# SCH_Front_Buzzer.net
KiCad netlist of a schematic drawn in Altium Designer
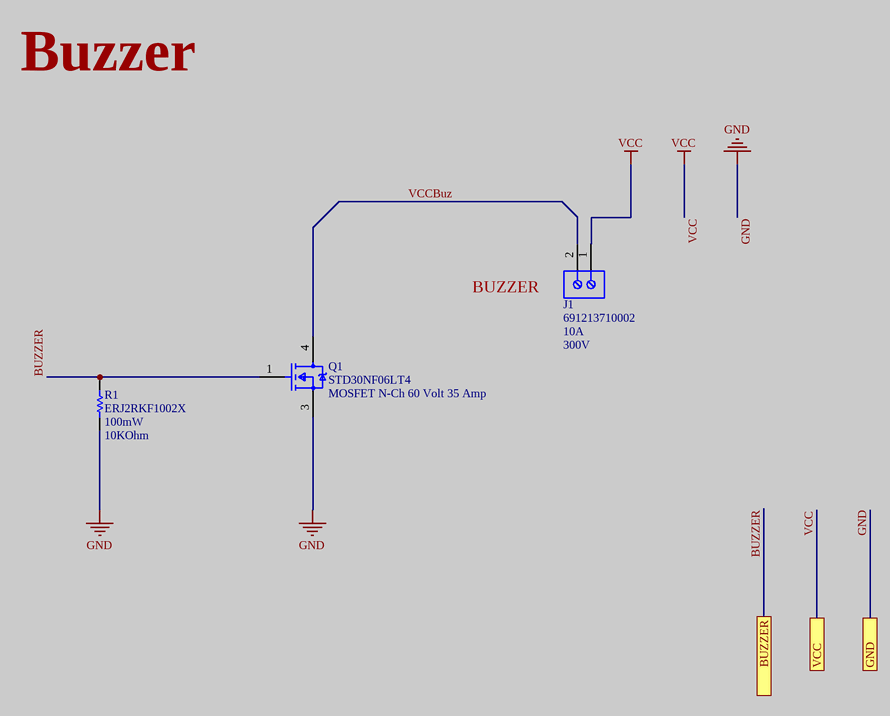
[diagram p0: SCH Front Buzzer.SchDoc]

(export (version "E")
  (design (tool "Eeschema 10.0.6"))
  (components
    (comp (ref "J1")
      (value "691213710002")
      (footprint "691213710002")
      (fields (field (name "CURRENT RATING") "10A") (field (name "VOLTAGE") "300V"))
      (libsource (lib "Altium Content Vault") (part "TBL - 1R - 02P - Screw"))
    )
    (comp (ref "Q1")
      (value "STD30NF06LT4")
      (footprint "FP-DPAK-P032P-MFG")
      (description "MOSFET N-CH 60V 35A DPAK")
      (fields
        (field (name "MOUSER DESCRIPTION") "MOSFET N-Ch 60 Volt 35 Amp")
        (field (name "MANUFACTURER") "STMicroelectronics")
        (field (name "OCTOPART") "https://octopart.com/std30nf06lt4-stmicroelectronics-39553433")
      )
      (libsource (lib "Altium Content Vault") (part "cdf1c68f84cb049e5ebc85739c3fcf6"))
    )
    (comp (ref "R1")
      (value "ERJ2RKF1002X")
      (footprint "RESC1005X40X25LL05T05")
      (description "Chip Resistor, 10 KOhm, +/- 1%, 0.1 W, -55 to 155 degC, 0402 (1005 Metric), RoHS, Tape and Reel")
      (fields
        (field (name "POWER RATING") "100mW")
        (field (name "RESISTANCE") "10KOhm")
        (field (name "TOLERANCE") "1%")
        (field (name "MANUFACTURER") "Panasonic")
      )
      (libsource (lib "Altium Content Vault") (part "RES-2"))
    )
  )
  (nets
    (net (code "1") (name "/BUZZER") (class "Default")
      (node (ref "Q1") (pin "1") (pinfunction "G_1") (pintype "passive"))
      (node (ref "R1") (pin "2") (pinfunction "2_2") (pintype "passive"))
    )
    (net (code "2") (name "/VCCBuz") (class "Default")
      (node (ref "J1") (pin "2") (pinfunction "2_2") (pintype "passive"))
      (node (ref "Q1") (pin "4") (pinfunction "D_4") (pintype "passive"))
    )
    (net (code "3") (name "GND") (class "Default")
      (node (ref "Q1") (pin "3") (pinfunction "S_3") (pintype "passive"))
      (node (ref "R1") (pin "1") (pinfunction "1_1") (pintype "passive"))
    )
    (net (code "4") (name "VCC") (class "Default")
      (node (ref "J1") (pin "1") (pinfunction "1_1") (pintype "passive"))
    )
  )
)
